# ESP8266.net
KiCad netlist of a schematic drawn in Altium Designer
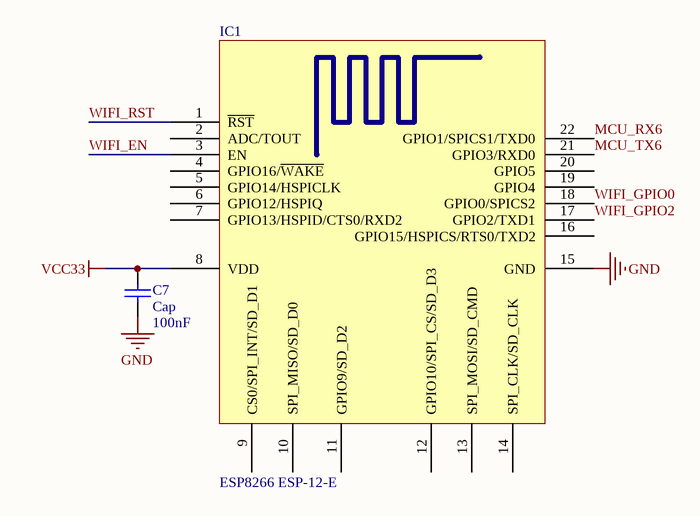
[diagram p0: ESP8266.SchDoc]

(export (version "E")
  (design (tool "Eeschema 10.0.6"))
  (components
    (comp (ref "C7")
      (value "Cap")
      (footprint "C0603")
      (description "Capacitor")
      (fields (field (name "ALTIUM_VALUE") "100nF") (field (name "PUBLISHER") "Altium Limited"))
      (libsource (lib "cadLib") (part "Cap"))
    )
    (comp (ref "IC1")
      (value "ESP8266 ESP-12-E")
      (footprint "ESP8266 ESP-12-E")
      (libsource (lib "cadLib") (part "ESP8266 ESP-12-E"))
    )
  )
  (nets
    (net (code "1") (name "/MCU_RX6") (class "Default")
      (node (ref "IC1") (pin "22") (pinfunction "GPIO1/SPICS1/TXD0_22") (pintype "passive"))
    )
    (net (code "2") (name "/MCU_TX6") (class "Default")
      (node (ref "IC1") (pin "21") (pinfunction "GPIO3/RXD0_21") (pintype "passive"))
    )
    (net (code "3") (name "/WIFI_EN") (class "Default")
      (node (ref "IC1") (pin "3") (pinfunction "EN_3") (pintype "passive"))
    )
    (net (code "4") (name "/WIFI_GPIO0") (class "Default")
      (node (ref "IC1") (pin "18") (pinfunction "GPIO0/SPICS2_18") (pintype "passive"))
    )
    (net (code "5") (name "/WIFI_GPIO2") (class "Default")
      (node (ref "IC1") (pin "17") (pinfunction "GPIO2/TXD1_17") (pintype "passive"))
    )
    (net (code "6") (name "/WIFI_RST") (class "Default")
      (node (ref "IC1") (pin "1") (pinfunction "~{RST}_1") (pintype "passive"))
    )
    (net (code "7") (name "GND") (class "Default")
      (node (ref "C7") (pin "1") (pinfunction "1_1") (pintype "passive"))
      (node (ref "IC1") (pin "15") (pinfunction "GND_15") (pintype "passive"))
    )
    (net (code "8") (name "VCC33") (class "Default")
      (node (ref "C7") (pin "2") (pinfunction "2_2") (pintype "passive"))
      (node (ref "IC1") (pin "8") (pinfunction "VDD_8") (pintype "passive"))
    )
    (net (code "9") (name "unconnected-(IC1-ADC{slash}TOUT-Pad2)") (class "Default")
      (node (ref "IC1") (pin "2") (pinfunction "ADC/TOUT_2") (pintype "passive"))
    )
    (net (code "10") (name "unconnected-(IC1-CS0{slash}SPI_INT{slash}SD_D1-Pad9)") (class "Default")
      (node (ref "IC1") (pin "9") (pinfunction "CS0/SPI_INT/SD_D1_9") (pintype "passive"))
    )
    (net (code "11") (name "unconnected-(IC1-GPIO4-Pad19)") (class "Default")
      (node (ref "IC1") (pin "19") (pinfunction "GPIO4_19") (pintype "passive"))
    )
    (net (code "12") (name "unconnected-(IC1-GPIO5-Pad20)") (class "Default")
      (node (ref "IC1") (pin "20") (pinfunction "GPIO5_20") (pintype "passive"))
    )
    (net (code "13") (name "unconnected-(IC1-GPIO9{slash}SD_D2-Pad11)") (class "Default")
      (node (ref "IC1") (pin "11") (pinfunction "GPIO9/SD_D2_11") (pintype "passive"))
    )
    (net (code "14") (name "unconnected-(IC1-GPIO10{slash}SPI_CS{slash}SD_D3-Pad12)") (class "Default")
      (node (ref "IC1") (pin "12") (pinfunction "GPIO10/SPI_CS/SD_D3_12") (pintype "passive"))
    )
    (net (code "15") (name "unconnected-(IC1-GPIO12{slash}HSPIQ-Pad6)") (class "Default")
      (node (ref "IC1") (pin "6") (pinfunction "GPIO12/HSPIQ_6") (pintype "passive"))
    )
    (net (code "16") (name "unconnected-(IC1-GPIO13{slash}HSPID{slash}CTS0{slash}RXD2-Pad7)") (class "Default")
      (node (ref "IC1") (pin "7") (pinfunction "GPIO13/HSPID/CTS0/RXD2_7") (pintype "passive"))
    )
    (net (code "17") (name "unconnected-(IC1-GPIO14{slash}HSPICLK-Pad5)") (class "Default")
      (node (ref "IC1") (pin "5") (pinfunction "GPIO14/HSPICLK_5") (pintype "passive"))
    )
    (net (code "18") (name "unconnected-(IC1-GPIO15{slash}HSPICS{slash}RTS0{slash}TXD2-Pad16)") (class "Default")
      (node (ref "IC1") (pin "16") (pinfunction "GPIO15/HSPICS/RTS0/TXD2_16") (pintype "passive"))
    )
    (net (code "19") (name "unconnected-(IC1-GPIO16{slash}~{WAKE}-Pad4)") (class "Default")
      (node (ref "IC1") (pin "4") (pinfunction "GPIO16/~{WAKE}_4") (pintype "passive"))
    )
    (net (code "20") (name "unconnected-(IC1-SPI_CLK{slash}SD_CLK-Pad14)") (class "Default")
      (node (ref "IC1") (pin "14") (pinfunction "SPI_CLK/SD_CLK_14") (pintype "passive"))
    )
    (net (code "21") (name "unconnected-(IC1-SPI_MISO{slash}SD_D0-Pad10)") (class "Default")
      (node (ref "IC1") (pin "10") (pinfunction "SPI_MISO/SD_D0_10") (pintype "passive"))
    )
    (net (code "22") (name "unconnected-(IC1-SPI_MOSI{slash}SD_CMD-Pad13)") (class "Default")
      (node (ref "IC1") (pin "13") (pinfunction "SPI_MOSI/SD_CMD_13") (pintype "passive"))
    )
  )
)
